# MSXIV_DC-DC_Converter.net
KiCad netlist of a schematic drawn in Altium Designer
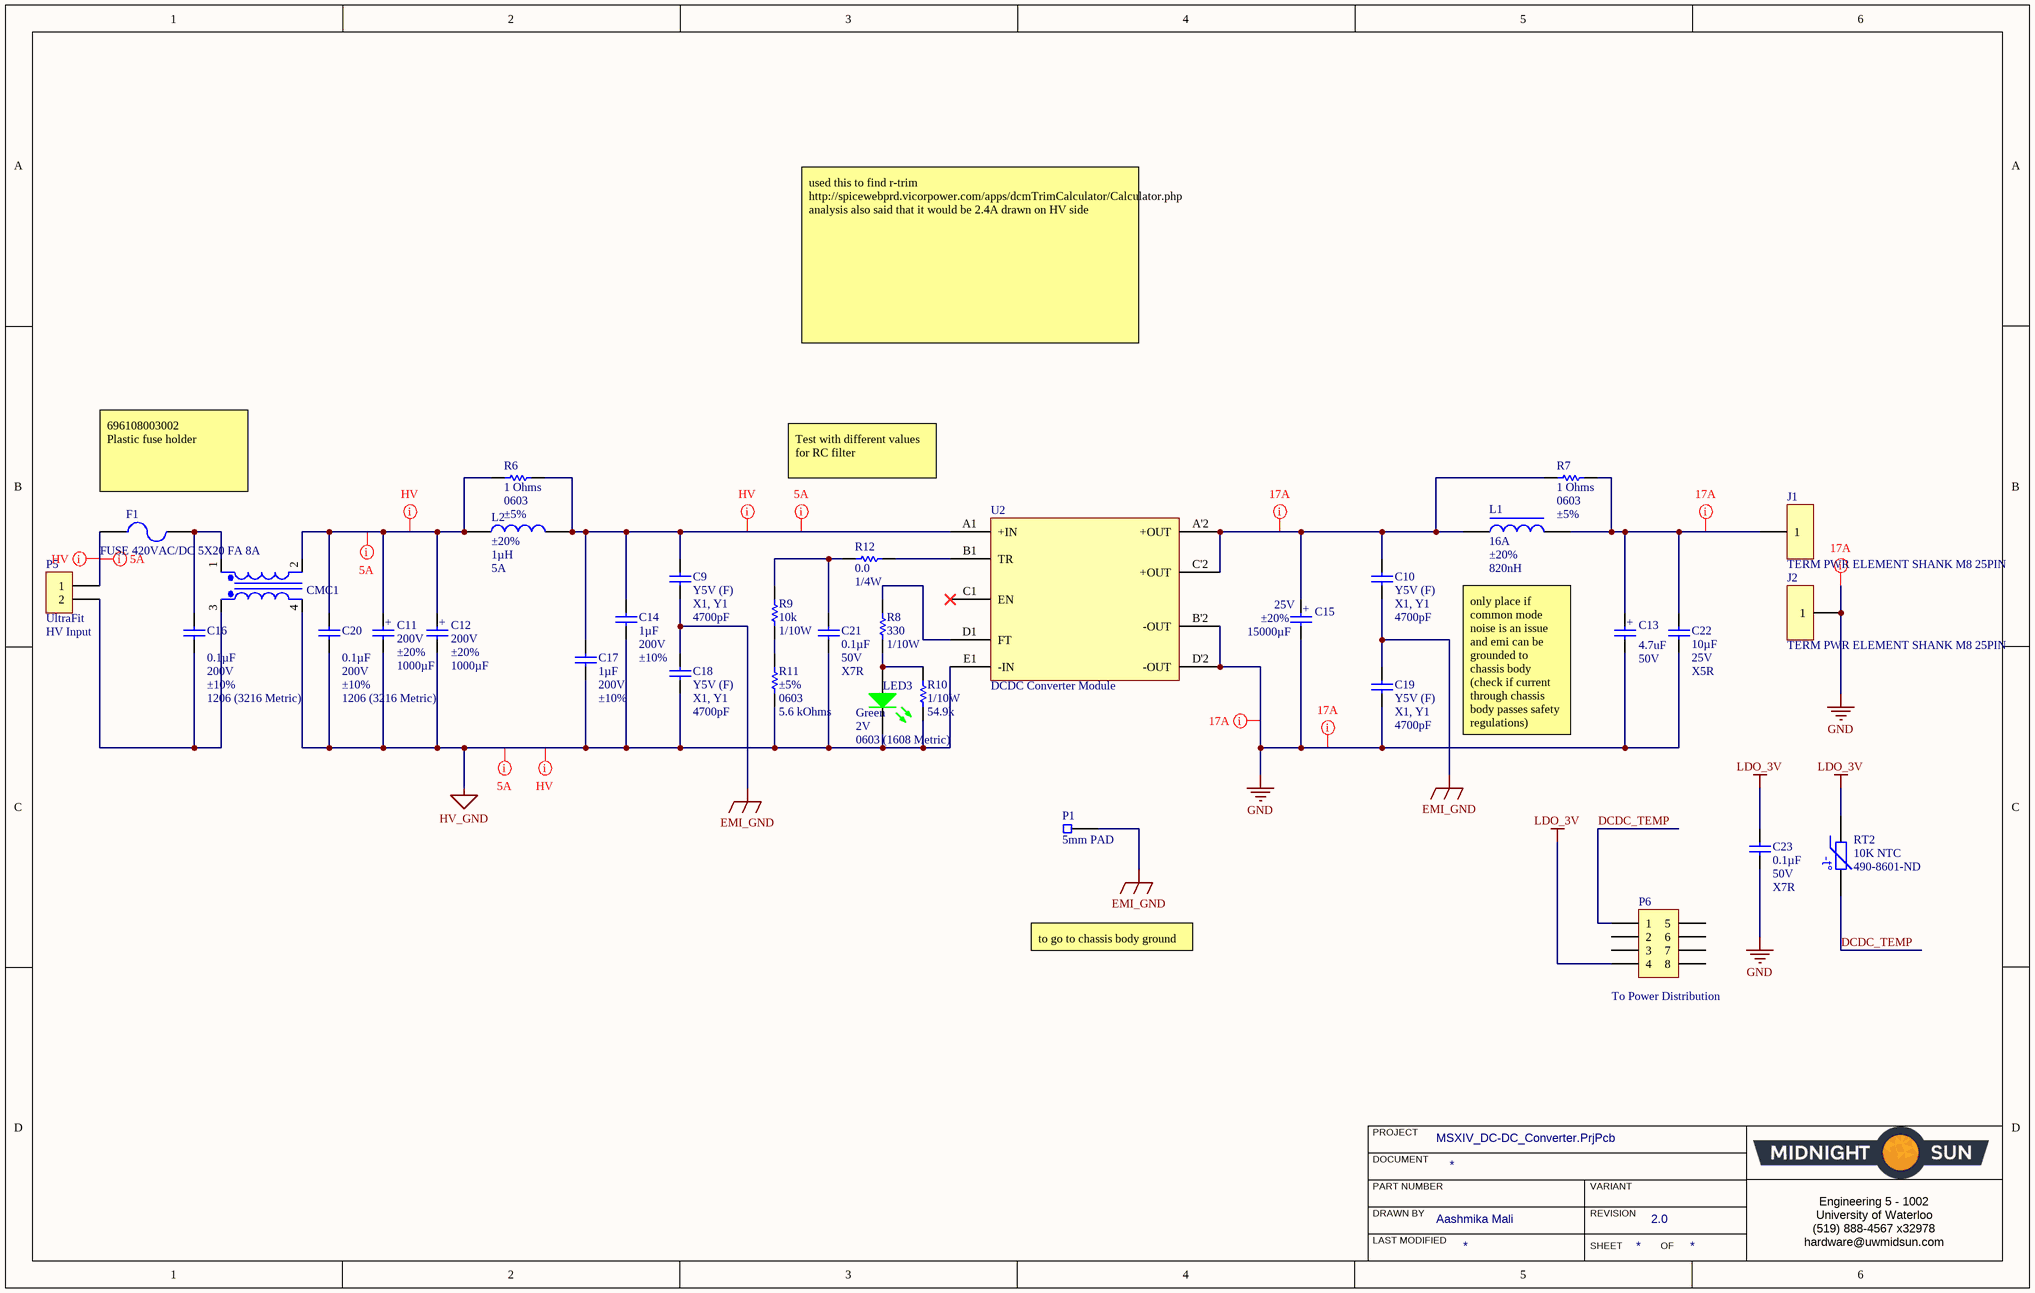
[diagram p0: MSXIV_DC-DC_Converter.SchDoc]

(export (version "E")
  (design (tool "Eeschema 10.0.6"))
  (components
    (comp (ref "C9")
      (value "4700pF")
      (footprint "CAP 4700PF 400VAC Y5V RADIAL")
      (description "4700pF ±20% 400VAC Ceramic Capacitor Y5V (F) Radial, Disc")
      (fields
        (field (name "MANUFACTURER") "KEMET")
        (field (name "MANUFACTURER PART NUMBER") "C951U472MVVDBA7317")
        (field (name "TEMPERATURE COEFFICIENT") "Y5V (F)")
        (field (name "RATINGS") "X1, Y1")
      )
      (libsource (lib "Schematic Diagrams") (part "CAP CER 4700PF 400VAC Y5V RADIAL"))
    )
    (comp (ref "C10")
      (value "4700pF")
      (footprint "CAP 4700PF 400VAC Y5V RADIAL")
      (description "4700pF ±20% 400VAC Ceramic Capacitor Y5V (F) Radial, Disc")
      (fields
        (field (name "MANUFACTURER") "KEMET")
        (field (name "MANUFACTURER PART NUMBER") "C951U472MVVDBA7317")
        (field (name "TEMPERATURE COEFFICIENT") "Y5V (F)")
        (field (name "RATINGS") "X1, Y1")
      )
      (libsource (lib "Schematic Diagrams") (part "CAP CER 4700PF 400VAC Y5V RADIAL"))
    )
    (comp (ref "C11")
      (value "CAP ALUM 1000UF 20% 200V SNAP")
      (footprint "CAP ALUM 1000uF 200V")
      (description "CAP RADIAL ALUM 1000UF 20% 200V SNAP")
      (fields
        (field (name "VOLTAGE - RATED") "200V")
        (field (name "TOLERANCE") "±20%")
        (field (name "CAPACITANCE") "1000µF")
      )
      (libsource (lib "Schematic Diagrams") (part "CAP ALUM 1000UF 20% 200V SNAP"))
    )
    (comp (ref "C12")
      (value "CAP ALUM 1000UF 20% 200V SNAP")
      (footprint "CAP ALUM 1000uF 200V")
      (description "CAP RADIAL ALUM 1000UF 20% 200V SNAP")
      (fields
        (field (name "VOLTAGE - RATED") "200V")
        (field (name "TOLERANCE") "±20%")
        (field (name "CAPACITANCE") "1000µF")
      )
      (libsource (lib "Schematic Diagrams") (part "CAP ALUM 1000UF 20% 200V SNAP"))
    )
    (comp (ref "C13")
      (value "EEE-1HA4R7NP")
      (footprint "CAP ALUM 6.3MM RADIAL SMD")
      (description "4.7µF 50V Aluminum Electrolytic Capacitors Radial, Can - SMD 2000 Hrs @ 85°C")
      (fields
        (field (name "TOLERANCE") "20%")
        (field (name "CAPACITANCE") "4.7uF")
        (field (name "VOLTAGE RATING (DC)") "50V")
      )
      (libsource (lib "Schematic Diagrams") (part "CAP ALUM 4.7UF 20% 50V SMD"))
    )
    (comp (ref "C14")
      (value "CAP CER 1UF 200V X7R 2220")
      (footprint "CAP, 2220")
      (description "1µF ±10% 200V Ceramic Capacitor X7R 2220 (5750 Metric)")
      (fields
        (field (name "MANUFACTURER") "Murata Electronics")
        (field (name "CAPACITANCE") "1µF")
        (field (name "VOLTAGE - RATED") "200V")
        (field (name "TOLERANCE") "±10%")
      )
      (libsource (lib "Schematic Diagrams") (part "CAP CER 1UF 200V X7R 2220"))
    )
    (comp (ref "C15")
      (value "CAP ALUM 15000UF 20% 25V SNAP")
      (footprint "CAP ALUM 1000uF 200V")
      (description "15000µF 25V Aluminum Electrolytic Capacitors Radial, Can - Snap-In 40mOhm 3000 Hrs @ 105°C")
      (fields
        (field (name "VOLTAGE - RATED") "25V")
        (field (name "TOLERANCE") "±20%")
        (field (name "CAPACITANCE") "15000µF")
        (field (name "MANUFACTURER") "Cornell Dubilier Electronics (CDE)")
        (field (name "MANUFACTURER PART NUMBER") "SLP153M025C4P3")
      )
      (libsource (lib "Schematic Diagrams") (part "CAP ALUM 15000UF 20% 25V SNAP"))
    )
    (comp (ref "C16")
      (value "CAP CER 0.1UF 200V X7R 1206")
      (footprint "CAP, 1206")
      (fields
        (field (name "CAPACITANCE") "0.1µF")
        (field (name "VOLTAGE - RATED") "200V")
        (field (name "TOLERANCE") "±10%")
        (field (name "PACKAGE / CASE") "1206 (3216 Metric)")
      )
      (libsource (lib "Schematic Diagrams") (part "CAP CER 0.1UF 200V X7R 1206"))
    )
    (comp (ref "C17")
      (value "CAP CER 1UF 200V X7R 2220")
      (footprint "CAP, 2220")
      (description "1µF ±10% 200V Ceramic Capacitor X7R 2220 (5750 Metric)")
      (fields
        (field (name "MANUFACTURER") "Murata Electronics")
        (field (name "CAPACITANCE") "1µF")
        (field (name "VOLTAGE - RATED") "200V")
        (field (name "TOLERANCE") "±10%")
      )
      (libsource (lib "Schematic Diagrams") (part "CAP CER 1UF 200V X7R 2220"))
    )
    (comp (ref "C18")
      (value "4700pF")
      (footprint "CAP 4700PF 400VAC Y5V RADIAL")
      (description "4700pF ±20% 400VAC Ceramic Capacitor Y5V (F) Radial, Disc")
      (fields
        (field (name "MANUFACTURER") "KEMET")
        (field (name "MANUFACTURER PART NUMBER") "C951U472MVVDBA7317")
        (field (name "TEMPERATURE COEFFICIENT") "Y5V (F)")
        (field (name "RATINGS") "X1, Y1")
      )
      (libsource (lib "Schematic Diagrams") (part "CAP CER 4700PF 400VAC Y5V RADIAL"))
    )
    (comp (ref "C19")
      (value "4700pF")
      (footprint "CAP 4700PF 400VAC Y5V RADIAL")
      (description "4700pF ±20% 400VAC Ceramic Capacitor Y5V (F) Radial, Disc")
      (fields
        (field (name "MANUFACTURER") "KEMET")
        (field (name "MANUFACTURER PART NUMBER") "C951U472MVVDBA7317")
        (field (name "TEMPERATURE COEFFICIENT") "Y5V (F)")
        (field (name "RATINGS") "X1, Y1")
      )
      (libsource (lib "Schematic Diagrams") (part "CAP CER 4700PF 400VAC Y5V RADIAL"))
    )
    (comp (ref "C20")
      (value "CAP CER 0.1UF 200V X7R 1206")
      (footprint "CAP, 1206")
      (fields
        (field (name "CAPACITANCE") "0.1µF")
        (field (name "VOLTAGE - RATED") "200V")
        (field (name "TOLERANCE") "±10%")
        (field (name "PACKAGE / CASE") "1206 (3216 Metric)")
      )
      (libsource (lib "Schematic Diagrams") (part "CAP CER 0.1UF 200V X7R 1206"))
    )
    (comp (ref "C21")
      (value "CAP CER 0.1UF 50V 10% X7R 0603")
      (footprint "CAP, 0603")
      (description "0.10µF ±10% 50V Ceramic Capacitor X7R 0603 (1608 Metric)")
      (fields
        (field (name "TOLERANCE") "±10%")
        (field (name "CAPACITANCE") "0.1µF")
        (field (name "VOLTAGE") "50V")
        (field (name "TEMPERATURE COEFFICIENT") "X7R")
      )
      (libsource (lib "Schematic Diagrams") (part "CAP CER 0.1UF 50V 10% X7R 0603"))
    )
    (comp (ref "C22")
      (value "CAP CER 10uF 25V 20% X5R 0603")
      (footprint "CAP, 0603")
      (description "10µF ±20% 25V Ceramic Capacitor X5R 0603 (1608 Metric)")
      (fields
        (field (name "TOLERANCE") "±20%")
        (field (name "CAPACITANCE") "10µF")
        (field (name "VOLTAGE") "25V")
        (field (name "TEMPERATURE COEFFICIENT") "X5R")
      )
      (libsource (lib "Schematic Diagrams") (part "CAP CER 10uF 25V 20% X5R 0603"))
    )
    (comp (ref "C23")
      (value "CAP CER 0.1UF 50V 10% X7R 0603")
      (footprint "CAP, 0603")
      (description "0.10µF ±10% 50V Ceramic Capacitor X7R 0603 (1608 Metric)")
      (fields
        (field (name "TOLERANCE") "±10%")
        (field (name "CAPACITANCE") "0.1µF")
        (field (name "VOLTAGE") "50V")
        (field (name "TEMPERATURE COEFFICIENT") "X7R")
      )
      (libsource (lib "Schematic Diagrams") (part "CAP CER 0.1UF 50V 10% X7R 0603"))
    )
    (comp (ref "CMC1")
      (value "CM Choke")
      (footprint "LCCI 50 Common mode choke")
      (description "2 Line Common Mode Choke Surface Mount  5.6A DCR 21mOhm")
      (fields (field (name "PARTNUMBER") "P0353NL"))
      (libsource (lib "Schematic Diagrams") (part "COMMON MODE CHOKE 5.6A 2LN SMD"))
    )
    (comp (ref "F1")
      (value "FUSE 420VAC/DC 5X20 FA 8A")
      (footprint "FUSE 420VAC/DC 5X20 FA 8A")
      (description "8A 420V AC 420V DC Fuse Cartridge, Ceramic Holder Cartridge, Non-Standard")
      (fields
        (field (name "MANUFACTURER PART NUMBER") "0487008.MXP")
        (field (name "MANUFACTURER") "Littelfuse Inc.")
      )
      (libsource (lib "Schematic Diagrams") (part "FUSE 420VAC/DC 5X20 FA 8A"))
    )
    (comp (ref "J1")
      (value "TERM PWR ELEMENT SHANK M8 25PIN")
      (footprint "TERM PWR ELEMENT SHANK M8 25PIN")
      (description "25 Pin Shank Terminal M8 Through Hole")
      (libsource (lib "Schematic Diagrams") (part "TERM PWR ELEMENT SHANK M8 25PIN"))
    )
    (comp (ref "J2")
      (value "TERM PWR ELEMENT SHANK M8 25PIN")
      (footprint "TERM PWR ELEMENT SHANK M8 25PIN")
      (description "25 Pin Shank Terminal M8 Through Hole")
      (libsource (lib "") (part "TERM PWR ELEMENT SHANK M8 25PIN_1"))
    )
    (comp (ref "L1")
      (value "IND 820NH 16A 6 MOHM SMD")
      (footprint "IND 820NH 16A 6 MOHM SMD")
      (description "820nH Shielded Molded Inductor 16A 6mOhm Max Nonstandard")
      (fields
        (field (name "MANUFACTURER PART NUMBER") "ECS-MPIL0630-R82MC")
        (field (name "MANUFACTURER") "ECS Inc.")
        (field (name "CURRENT RATING (AMPS)") "16A")
        (field (name "TOLERANCE") "±20%")
        (field (name "INDUCTANCE") "820nH")
      )
      (libsource (lib "Schematic Diagrams") (part "IND 820NH 16A 6 MOHM SMD"))
    )
    (comp (ref "L2")
      (value "IND 1UH 5A 12MOHM SMD")
      (footprint "IND 1UH 5A 12MOHM SMD")
      (description "1µH Semi-Shielded Wirewound Inductor 5A 12mOhm Nonstandard")
      (fields
        (field (name "TOLERANCE") "±20%")
        (field (name "INDUCTANCE") "1µH")
        (field (name "CURRENT RATING (AMPS)") "5A")
      )
      (libsource (lib "Schematic Diagrams") (part "IND 1uH 5A 12MOHM SMD"))
    )
    (comp (ref "LED3")
      (value "LED GREEN CLEAR 2V 0603")
      (footprint "LED_0603")
      (description "Green 572nm LED Indication - Discrete 2V 0603 (1608 Metric)")
      (fields
        (field (name "MANUFACTURER") "Wurth Electronics Inc.")
        (field (name "MANUFACTURER PART NUMBER") "150060VS75000")
        (field (name "PACKAGE / CASE") "0603 (1608 Metric)")
        (field (name "COLOR") "Green")
        (field (name "VOLTAGE - FORWARD (VF) (TYP)") "2V")
      )
      (libsource (lib "Schematic Diagrams") (part "LED GREEN CLEAR 2V 0603"))
    )
    (comp (ref "P1")
      (value "5mm PAD")
      (footprint "5mm PAD")
      (description "5x5mm pad to solder 16 gauge wire")
      (libsource (lib "Schematic Diagrams") (part "5mm PAD"))
    )
    (comp (ref "P5")
      (value "CONN 2POS ULTRA-FIT 0.138\"")
      (footprint "CONN, 2POS ULTRA-FIT")
      (description "2 Positions Header, Shrouded Connector 0.138\" (3.50mm) Through Hole Gold")
      (fields (field (name "VOLTAGE") "400V") (field (name "SERIES") "UltraFit"))
      (libsource (lib "Schematic Diagrams") (part "CONN 2POS ULTRA-FIT 0.138{dblquote}"))
    )
    (comp (ref "P6")
      (value "CONN 8POS ULTRA-FIT 0.138\"")
      (footprint "CONN, 8POS ULTRA-FIT")
      (description "8 Positions Header Connector 0.138\" (3.50mm) Through Hole Tin")
      (fields
        (field (name "MANUFACTURER") "Molex, LLC")
        (field (name "MANUFACTURER PART NUMBER") "1722991108")
      )
      (libsource (lib "Schematic Diagrams") (part "CONN 8POS ULTRA-FIT 0.138{dblquote}"))
    )
    (comp (ref "R6")
      (value "RES 1 OHM 5% 1/10W 0603")
      (footprint "RES, 0603")
      (description "RES SMD 1 OHM 5% 1/10W 0603")
      (fields
        (field (name "DIGI-KEY PART NUMBER") "RHM1.0AZCT-ND")
        (field (name "RESISTANCE") "1 Ohms")
        (field (name "SUPPLIER DEVICE PACKAGE") "0603")
        (field (name "TOLERANCE") "±5%")
      )
      (libsource (lib "Schematic Diagrams") (part "RES 1 OHM 5% 1/10W 0603"))
    )
    (comp (ref "R7")
      (value "RES 1 OHM 5% 1/10W 0603")
      (footprint "RES, 0603")
      (description "RES SMD 1 OHM 5% 1/10W 0603")
      (fields
        (field (name "DIGI-KEY PART NUMBER") "RHM1.0AZCT-ND")
        (field (name "RESISTANCE") "1 Ohms")
        (field (name "SUPPLIER DEVICE PACKAGE") "0603")
        (field (name "TOLERANCE") "±5%")
      )
      (libsource (lib "Schematic Diagrams") (part "RES 1 OHM 5% 1/10W 0603"))
    )
    (comp (ref "R8")
      (value "RES 330 OHM 1% 1/10W 0603")
      (footprint "RES, 0603")
      (fields
        (field (name "MANUFACTURER") "TE Connectivity")
        (field (name "MANUFACTURER PART NUMBER") "1-2176339-9")
        (field (name "RESISTANCE") "330")
        (field (name "POWER") "1/10W")
      )
      (libsource (lib "Schematic Diagrams") (part "RES 330 OHM 1% 1/10W 0603"))
    )
    (comp (ref "R9")
      (value "RES 10K OHM 1% 1/10W 0603")
      (footprint "RES, 0603")
      (description "RES SMD 10K OHM 1% 1/10W 0603")
      (fields
        (field (name "TOLERANCE") "±1%")
        (field (name "RESISTANCE") "10k")
        (field (name "POWER") "1/10W")
      )
      (libsource (lib "Schematic Diagrams") (part "RES 10K OHM 1% 1/10W 0603"))
    )
    (comp (ref "R10")
      (value "RES 54.9K OHM 1% 1/10W 0603")
      (footprint "RES, 0603")
      (description "54.9k Ohm ±1% 0.1W, 1/10W Chip Resistor 0603 (1608 Metric) Automotive AEC-Q200 Thick Film")
      (fields
        (field (name "MANUFACTURER") "Panasonic Electronic Components")
        (field (name "MANUFACTURER PART NUMBER") "ERJ-3EKF5492V")
        (field (name "POWER (WATTS)") "1/10W")
        (field (name "RESISTANCE (OHMS)") "54.9k")
      )
      (libsource (lib "Schematic Diagrams") (part "RES 54.9K OHM 1% 1/10W 0603"))
    )
    (comp (ref "R11")
      (value "RES 15.6K OHM 0.1% 1/10W 0402")
      (footprint "RES, 0603")
      (description "5.6 kOhms ±5% 0.1W, 1/10W Chip Resistor 0603 (1608 Metric) Moisture Resistant Thick Film")
      (fields
        (field (name "TOLERANCE") "±5%")
        (field (name "SUPPLIER DEVICE PACKAGE") "0603")
        (field (name "RESISTANCE") "5.6 kOhms")
      )
      (libsource (lib "Schematic Diagrams") (part "RES 5.6K OHM 5% 1/10W 0603"))
    )
    (comp (ref "R12")
      (value "RES 0.0 OHM 1/4W 0603")
      (footprint "RES, 0603")
      (description "RES SMD 0.0 OHM JUMPER 1/4W 0603")
      (fields (field (name "RESISTANCE") "0.0") (field (name "POWER (WATTS)") "1/4W"))
      (libsource (lib "Schematic Diagrams") (part "RES 0.0 OHM 1/4W 0603"))
    )
    (comp (ref "RT2")
      (value "10K NTC")
      (footprint "NTC THERMISTOR BEAD")
      (description "NTC Thermistor 10k Bead")
      (fields
        (field (name "MANUFACTURER") "Murata Electronics North America")
        (field (name "MANUFACTURER PART NUMBER") "NXRT15XH103FA1B030")
        (field (name "SUPPLIER PART NUMBER 1") "490-8601-ND")
      )
      (libsource (lib "Schematic Diagrams") (part "NTC THERMISTOR 10K 1% BEAD"))
    )
    (comp (ref "U2")
      (value "DCDC VICOR CONVERTER 15V 240W - DCM3623TA5N17B4T70")
      (footprint "IC, DCDC converter DCM3623TA5N17B4T70")
      (description "DC DC CONVERTER 15V 240W")
      (fields (field (name "POWER") "240W") (field (name "TYPE") "DCDC Converter Module"))
      (libsource (lib "Schematic Diagrams") (part "DCDC VICOR CONVERTER 15V 240W - DCM3623TA5N17B4T70"))
    )
  )
  (nets
    (net (code "1") (name "/DCDC_TEMP") (class "Default")
      (node (ref "P6") (pin "1") (pinfunction "1_1") (pintype "passive"))
      (node (ref "RT2") (pin "2") (pinfunction "2_2") (pintype "passive"))
    )
    (net (code "2") (name "EMI_GND") (class "Default")
      (node (ref "C10") (pin "2") (pinfunction "2_2") (pintype "passive"))
      (node (ref "C18") (pin "1") (pinfunction "1_1") (pintype "passive"))
      (node (ref "C19") (pin "1") (pinfunction "1_1") (pintype "passive"))
      (node (ref "C9") (pin "2") (pinfunction "2_2") (pintype "passive"))
      (node (ref "P1") (pin "1") (pinfunction "1_1") (pintype "passive"))
    )
    (net (code "3") (name "GND") (class "Default")
      (node (ref "C13") (pin "2") (pinfunction "2_2") (pintype "passive"))
      (node (ref "C15") (pin "2") (pinfunction "2_2") (pintype "passive"))
      (node (ref "C19") (pin "2") (pinfunction "2_2") (pintype "passive"))
      (node (ref "C22") (pin "2") (pinfunction "2_2") (pintype "passive"))
      (node (ref "C23") (pin "2") (pinfunction "2_2") (pintype "passive"))
      (node (ref "J2") (pin "1") (pinfunction "1_1") (pintype "passive"))
      (node (ref "U2") (pin "B'2") (pinfunction "-OUT_B'2") (pintype "passive"))
      (node (ref "U2") (pin "D'2") (pinfunction "-OUT_D'2") (pintype "passive"))
    )
    (net (code "4") (name "HV_GND") (class "Default")
      (node (ref "C11") (pin "2") (pinfunction "2_2") (pintype "passive"))
      (node (ref "C12") (pin "2") (pinfunction "2_2") (pintype "passive"))
      (node (ref "C14") (pin "2") (pinfunction "2_2") (pintype "passive"))
      (node (ref "C17") (pin "2") (pinfunction "2_2") (pintype "passive"))
      (node (ref "C18") (pin "2") (pinfunction "2_2") (pintype "passive"))
      (node (ref "C20") (pin "2") (pinfunction "2_2") (pintype "passive"))
      (node (ref "C21") (pin "2") (pinfunction "2_2") (pintype "passive"))
      (node (ref "CMC1") (pin "4") (pintype "passive"))
      (node (ref "LED3") (pin "2") (pinfunction "K_2") (pintype "passive"))
      (node (ref "R10") (pin "2") (pinfunction "2_2") (pintype "passive"))
      (node (ref "R11") (pin "1") (pinfunction "1_1") (pintype "passive"))
      (node (ref "U2") (pin "E1") (pinfunction "-IN_E1") (pintype "passive"))
    )
    (net (code "5") (name "LDO_3V") (class "Default")
      (node (ref "C23") (pin "1") (pinfunction "1_1") (pintype "passive"))
      (node (ref "P6") (pin "4") (pinfunction "4_4") (pintype "passive"))
      (node (ref "RT2") (pin "1") (pinfunction "1_1") (pintype "passive"))
    )
    (net (code "6") (name "Net-(C10-Pad1)") (class "Default")
      (node (ref "C10") (pin "1") (pinfunction "1_1") (pintype "passive"))
      (node (ref "C15") (pin "1") (pinfunction "1_1") (pintype "passive"))
      (node (ref "L1") (pin "1") (pinfunction "1_1") (pintype "passive"))
      (node (ref "R7") (pin "1") (pinfunction "1_1") (pintype "passive"))
      (node (ref "U2") (pin "A'2") (pinfunction "+OUT_A'2") (pintype "passive"))
      (node (ref "U2") (pin "C'2") (pinfunction "+OUT_C'2") (pintype "passive"))
    )
    (net (code "7") (name "Net-(C11-Pad1)") (class "Default")
      (node (ref "C11") (pin "1") (pinfunction "1_1") (pintype "passive"))
      (node (ref "C12") (pin "1") (pinfunction "1_1") (pintype "passive"))
      (node (ref "C20") (pin "1") (pinfunction "1_1") (pintype "passive"))
      (node (ref "CMC1") (pin "2") (pintype "passive"))
      (node (ref "L2") (pin "1") (pinfunction "1_1") (pintype "passive"))
      (node (ref "R6") (pin "1") (pinfunction "1_1") (pintype "passive"))
    )
    (net (code "8") (name "Net-(C13-Pad1)") (class "Default")
      (node (ref "C13") (pin "1") (pinfunction "1_1") (pintype "passive"))
      (node (ref "C22") (pin "1") (pinfunction "1_1") (pintype "passive"))
      (node (ref "J1") (pin "1") (pinfunction "1_1") (pintype "passive"))
      (node (ref "L1") (pin "2") (pinfunction "2_2") (pintype "passive"))
      (node (ref "R7") (pin "2") (pinfunction "2_2") (pintype "passive"))
    )
    (net (code "9") (name "Net-(C16-Pad1)") (class "Default")
      (node (ref "C16") (pin "1") (pinfunction "1_1") (pintype "passive"))
      (node (ref "CMC1") (pin "1") (pintype "passive"))
      (node (ref "F1") (pin "2") (pinfunction "2_2") (pintype "passive"))
    )
    (net (code "10") (name "Net-(C16-Pad2)") (class "Default")
      (node (ref "C16") (pin "2") (pinfunction "2_2") (pintype "passive"))
      (node (ref "CMC1") (pin "3") (pintype "passive"))
      (node (ref "P5") (pin "2") (pinfunction "2_2") (pintype "passive"))
    )
    (net (code "11") (name "Net-(C21-Pad1)") (class "Default")
      (node (ref "C21") (pin "1") (pinfunction "1_1") (pintype "passive"))
      (node (ref "R12") (pin "1") (pinfunction "1_1") (pintype "passive"))
      (node (ref "R9") (pin "1") (pinfunction "1_1") (pintype "passive"))
    )
    (net (code "12") (name "Net-(F1-Pad1)") (class "Default")
      (node (ref "F1") (pin "1") (pinfunction "1_1") (pintype "passive"))
      (node (ref "P5") (pin "1") (pinfunction "1_1") (pintype "passive"))
    )
    (net (code "13") (name "Net-(LED3-A)") (class "Default")
      (node (ref "LED3") (pin "1") (pinfunction "A_1") (pintype "passive"))
      (node (ref "R10") (pin "1") (pinfunction "1_1") (pintype "passive"))
      (node (ref "R8") (pin "2") (pinfunction "2_2") (pintype "passive"))
    )
    (net (code "14") (name "Net-(R11-Pad2)") (class "Default")
      (node (ref "R11") (pin "2") (pinfunction "2_2") (pintype "passive"))
      (node (ref "R9") (pin "2") (pinfunction "2_2") (pintype "passive"))
    )
    (net (code "15") (name "Net-(U2-+IN)") (class "Default")
      (node (ref "C14") (pin "1") (pinfunction "1_1") (pintype "passive"))
      (node (ref "C17") (pin "1") (pinfunction "1_1") (pintype "passive"))
      (node (ref "C9") (pin "1") (pinfunction "1_1") (pintype "passive"))
      (node (ref "L2") (pin "2") (pinfunction "2_2") (pintype "passive"))
      (node (ref "R6") (pin "2") (pinfunction "2_2") (pintype "passive"))
      (node (ref "U2") (pin "A1") (pinfunction "+IN_A1") (pintype "passive"))
    )
    (net (code "16") (name "Net-(U2-FT)") (class "Default")
      (node (ref "R8") (pin "1") (pinfunction "1_1") (pintype "passive"))
      (node (ref "U2") (pin "D1") (pinfunction "FT_D1") (pintype "passive"))
    )
    (net (code "17") (name "Net-(U2-TR)") (class "Default")
      (node (ref "R12") (pin "2") (pinfunction "2_2") (pintype "passive"))
      (node (ref "U2") (pin "B1") (pinfunction "TR_B1") (pintype "passive"))
    )
    (net (code "18") (name "unconnected-(P6-Pad2)") (class "Default")
      (node (ref "P6") (pin "2") (pinfunction "2_2") (pintype "passive"))
    )
    (net (code "19") (name "unconnected-(P6-Pad3)") (class "Default")
      (node (ref "P6") (pin "3") (pinfunction "3_3") (pintype "passive"))
    )
    (net (code "20") (name "unconnected-(P6-Pad5)") (class "Default")
      (node (ref "P6") (pin "5") (pinfunction "5_5") (pintype "passive"))
    )
    (net (code "21") (name "unconnected-(P6-Pad6)") (class "Default")
      (node (ref "P6") (pin "6") (pinfunction "6_6") (pintype "passive"))
    )
    (net (code "22") (name "unconnected-(P6-Pad7)") (class "Default")
      (node (ref "P6") (pin "7") (pinfunction "7_7") (pintype "passive"))
    )
    (net (code "23") (name "unconnected-(P6-Pad8)") (class "Default")
      (node (ref "P6") (pin "8") (pinfunction "8_8") (pintype "passive"))
    )
    (net (code "24") (name "unconnected-(U2-EN-PadC1)") (class "Default")
      (node (ref "U2") (pin "C1") (pinfunction "EN_C1") (pintype "passive+no_connect"))
    )
  )
)
